# ATTinyx5_Utility_Board.net
KiCad netlist of a schematic drawn in EAGLE
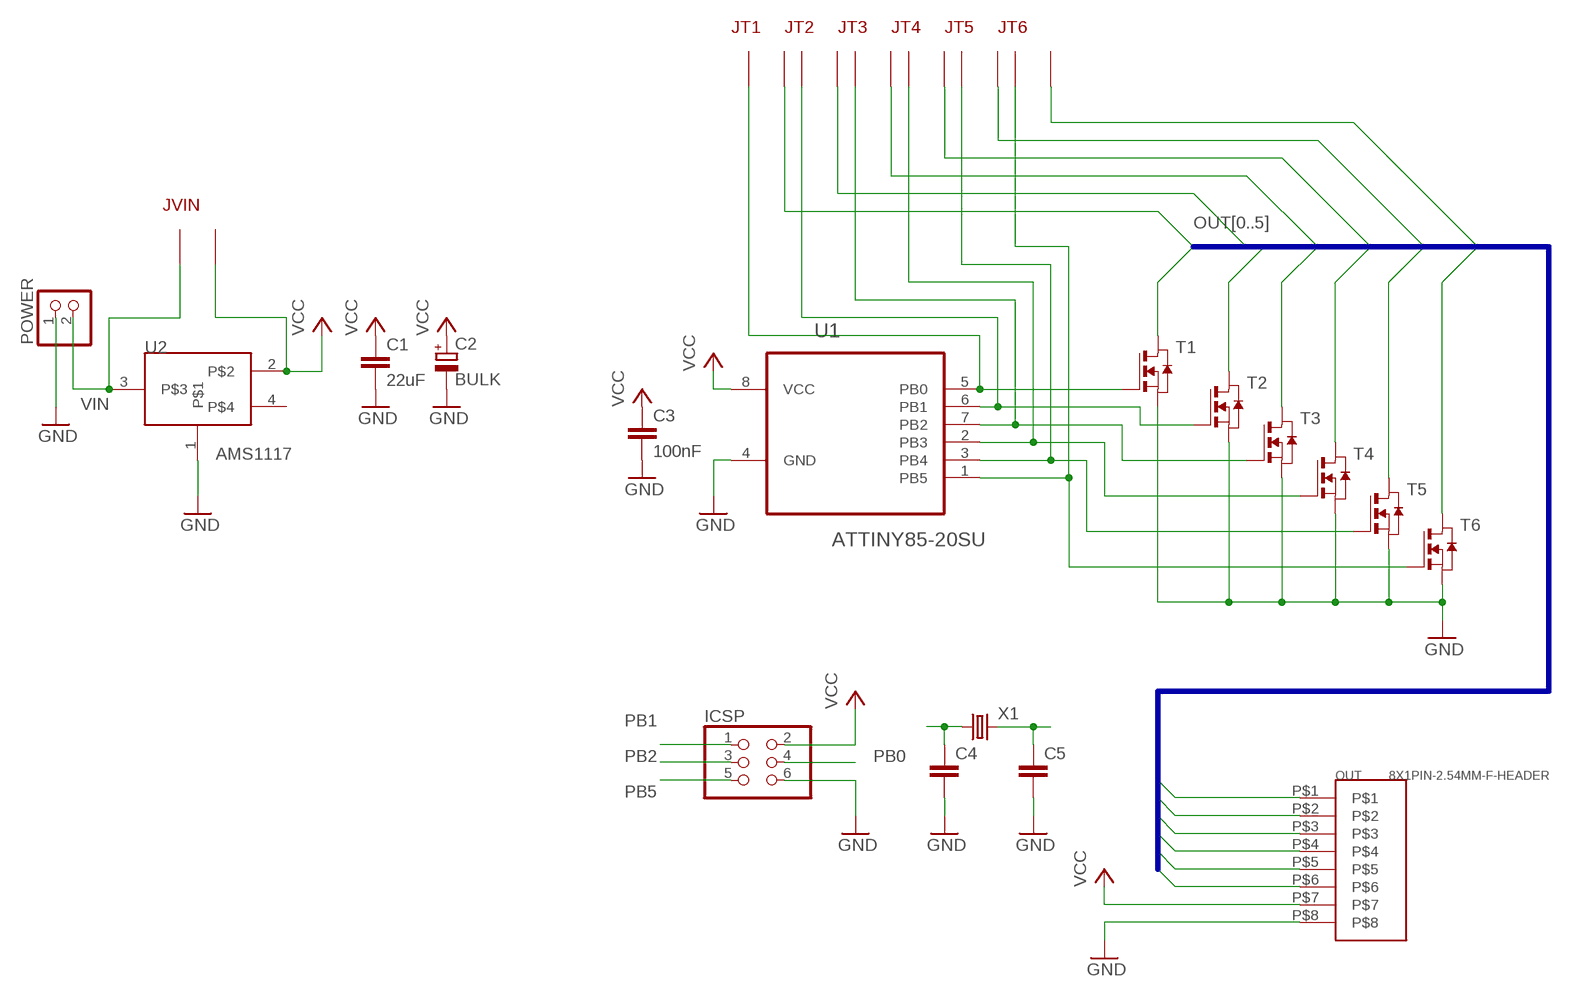
[diagram p0: schematic, sheet 1]

(export (version "E")
  (design (tool "Eeschema 10.0.6"))
  (components
    (comp (ref "C1")
      (value "22uF")
      (footprint "eagle-import:C1206")
      (libsource (lib "eagle-import") (part "C-EUC1206"))
    )
    (comp (ref "C2")
      (value "BULK")
      (footprint "eagle-import:E3,5-10")
      (libsource (lib "eagle-import") (part "CPOL-EUE3.5-10"))
    )
    (comp (ref "C3")
      (value "100nF")
      (footprint "eagle-import:C0805")
      (libsource (lib "eagle-import") (part "C-EUC0805"))
    )
    (comp (ref "C4")
      (value "C-EUC0805")
      (footprint "eagle-import:C0805")
      (libsource (lib "eagle-import") (part "C-EUC0805"))
    )
    (comp (ref "C5")
      (value "C-EUC0805")
      (footprint "eagle-import:C0805")
      (libsource (lib "eagle-import") (part "C-EUC0805"))
    )
    (comp (ref "ICSP")
      (value "PINHD-2X3")
      (footprint "eagle-import:2X03")
      (libsource (lib "eagle-import") (part "PINHD-2X3"))
    )
    (comp (ref "JT1")
      (value "SOLDER_JUMPER")
      (footprint "eagle-import:1206")
      (libsource (lib "eagle-import") (part "SOLDER_JUMPER"))
    )
    (comp (ref "JT2")
      (value "SOLDER_JUMPER")
      (footprint "eagle-import:1206")
      (libsource (lib "eagle-import") (part "SOLDER_JUMPER"))
    )
    (comp (ref "JT3")
      (value "SOLDER_JUMPER")
      (footprint "eagle-import:1206")
      (libsource (lib "eagle-import") (part "SOLDER_JUMPER"))
    )
    (comp (ref "JT4")
      (value "SOLDER_JUMPER")
      (footprint "eagle-import:1206")
      (libsource (lib "eagle-import") (part "SOLDER_JUMPER"))
    )
    (comp (ref "JT5")
      (value "SOLDER_JUMPER")
      (footprint "eagle-import:1206")
      (libsource (lib "eagle-import") (part "SOLDER_JUMPER"))
    )
    (comp (ref "JT6")
      (value "SOLDER_JUMPER")
      (footprint "eagle-import:1206")
      (libsource (lib "eagle-import") (part "SOLDER_JUMPER"))
    )
    (comp (ref "JVIN")
      (value "SOLDER_JUMPER")
      (footprint "eagle-import:1206")
      (libsource (lib "eagle-import") (part "SOLDER_JUMPER"))
    )
    (comp (ref "OUT")
      (value "8X1PIN-2.54MM-F-HEADER")
      (footprint "eagle-import:8X1-2.54MM")
      (libsource (lib "eagle-import") (part "8X1PIN-2.54MM-F-HEADER"))
    )
    (comp (ref "POWER")
      (value "PINHD-1X2")
      (footprint "eagle-import:1X02")
      (libsource (lib "eagle-import") (part "PINHD-1X2"))
    )
    (comp (ref "T1")
      (value "NMOSSOT23")
      (footprint "eagle-import:SOT-23")
      (libsource (lib "eagle-import") (part "NMOSSOT23"))
    )
    (comp (ref "T2")
      (value "NMOSSOT23")
      (footprint "eagle-import:SOT-23")
      (libsource (lib "eagle-import") (part "NMOSSOT23"))
    )
    (comp (ref "T3")
      (value "NMOSSOT23")
      (footprint "eagle-import:SOT-23")
      (libsource (lib "eagle-import") (part "NMOSSOT23"))
    )
    (comp (ref "T4")
      (value "NMOSSOT23")
      (footprint "eagle-import:SOT-23")
      (libsource (lib "eagle-import") (part "NMOSSOT23"))
    )
    (comp (ref "T5")
      (value "NMOSSOT23")
      (footprint "eagle-import:SOT-23")
      (libsource (lib "eagle-import") (part "NMOSSOT23"))
    )
    (comp (ref "T6")
      (value "NMOSSOT23")
      (footprint "eagle-import:SOT-23")
      (libsource (lib "eagle-import") (part "NMOSSOT23"))
    )
    (comp (ref "U1")
      (value "ATTINY85-20SU")
      (footprint "eagle-import:SOIC127P798X216-8N")
      (libsource (lib "eagle-import") (part "ATTINY85-20SU"))
    )
    (comp (ref "U2")
      (value "AMS1117")
      (footprint "eagle-import:SOT223")
      (libsource (lib "eagle-import") (part "ASM1117-3.3"))
    )
    (comp (ref "X1")
      (value "CRYSTALSM49")
      (footprint "eagle-import:SM49")
      (libsource (lib "eagle-import") (part "CRYSTALSM49"))
    )
  )
  (nets
    (net (code "1") (name "/OUT0") (class "Default")
      (node (ref "JT1") (pin "P$2") (pinfunction "P$2_P$2") (pintype "bidirectional"))
      (node (ref "OUT") (pin "P$1") (pinfunction "P$1_P$1") (pintype "bidirectional"))
      (node (ref "T1") (pin "1") (pinfunction "D_1") (pintype "passive"))
    )
    (net (code "2") (name "/OUT1") (class "Default")
      (node (ref "JT2") (pin "P$2") (pinfunction "P$2_P$2") (pintype "bidirectional"))
      (node (ref "OUT") (pin "P$2") (pinfunction "P$2_P$2") (pintype "bidirectional"))
      (node (ref "T2") (pin "1") (pinfunction "D_1") (pintype "passive"))
    )
    (net (code "3") (name "/OUT2") (class "Default")
      (node (ref "JT3") (pin "P$2") (pinfunction "P$2_P$2") (pintype "bidirectional"))
      (node (ref "OUT") (pin "P$3") (pinfunction "P$3_P$3") (pintype "bidirectional"))
      (node (ref "T3") (pin "1") (pinfunction "D_1") (pintype "passive"))
    )
    (net (code "4") (name "/OUT3") (class "Default")
      (node (ref "JT4") (pin "P$2") (pinfunction "P$2_P$2") (pintype "bidirectional"))
      (node (ref "OUT") (pin "P$4") (pinfunction "P$4_P$4") (pintype "bidirectional"))
      (node (ref "T4") (pin "1") (pinfunction "D_1") (pintype "passive"))
    )
    (net (code "5") (name "/OUT4") (class "Default")
      (node (ref "JT5") (pin "P$2") (pinfunction "P$2_P$2") (pintype "bidirectional"))
      (node (ref "OUT") (pin "P$5") (pinfunction "P$5_P$5") (pintype "bidirectional"))
      (node (ref "T5") (pin "1") (pinfunction "D_1") (pintype "passive"))
    )
    (net (code "6") (name "/OUT5") (class "Default")
      (node (ref "JT6") (pin "P$2") (pinfunction "P$2_P$2") (pintype "bidirectional"))
      (node (ref "OUT") (pin "P$6") (pinfunction "P$6_P$6") (pintype "bidirectional"))
      (node (ref "T6") (pin "1") (pinfunction "D_1") (pintype "passive"))
    )
    (net (code "7") (name "/PB0") (class "Default")
      (node (ref "ICSP") (pin "4") (pinfunction "4_4") (pintype "passive"))
      (node (ref "JT1") (pin "P$1") (pinfunction "P$1_P$1") (pintype "bidirectional"))
      (node (ref "T1") (pin "3") (pinfunction "G_3") (pintype "passive"))
      (node (ref "U1") (pin "5") (pinfunction "PB0_5") (pintype "bidirectional"))
    )
    (net (code "8") (name "/PB1") (class "Default")
      (node (ref "ICSP") (pin "1") (pinfunction "1_1") (pintype "passive"))
      (node (ref "JT2") (pin "P$1") (pinfunction "P$1_P$1") (pintype "bidirectional"))
      (node (ref "T2") (pin "3") (pinfunction "G_3") (pintype "passive"))
      (node (ref "U1") (pin "6") (pinfunction "PB1_6") (pintype "bidirectional"))
    )
    (net (code "9") (name "/PB2") (class "Default")
      (node (ref "ICSP") (pin "3") (pinfunction "3_3") (pintype "passive"))
      (node (ref "JT3") (pin "P$1") (pinfunction "P$1_P$1") (pintype "bidirectional"))
      (node (ref "T3") (pin "3") (pinfunction "G_3") (pintype "passive"))
      (node (ref "U1") (pin "7") (pinfunction "PB2_7") (pintype "bidirectional"))
    )
    (net (code "10") (name "/PB3") (class "Default")
      (node (ref "C4") (pin "1") (pinfunction "1_1") (pintype "passive"))
      (node (ref "JT4") (pin "P$1") (pinfunction "P$1_P$1") (pintype "bidirectional"))
      (node (ref "T4") (pin "3") (pinfunction "G_3") (pintype "passive"))
      (node (ref "U1") (pin "2") (pinfunction "PB3_2") (pintype "bidirectional"))
      (node (ref "X1") (pin "1") (pinfunction "1_1") (pintype "passive"))
    )
    (net (code "11") (name "/PB4") (class "Default")
      (node (ref "C5") (pin "1") (pinfunction "1_1") (pintype "passive"))
      (node (ref "JT5") (pin "P$1") (pinfunction "P$1_P$1") (pintype "bidirectional"))
      (node (ref "T5") (pin "3") (pinfunction "G_3") (pintype "passive"))
      (node (ref "U1") (pin "3") (pinfunction "PB4_3") (pintype "bidirectional"))
      (node (ref "X1") (pin "2") (pinfunction "2_2") (pintype "passive"))
    )
    (net (code "12") (name "/PB5") (class "Default")
      (node (ref "ICSP") (pin "5") (pinfunction "5_5") (pintype "passive"))
      (node (ref "JT6") (pin "P$1") (pinfunction "P$1_P$1") (pintype "bidirectional"))
      (node (ref "T6") (pin "3") (pinfunction "G_3") (pintype "passive"))
      (node (ref "U1") (pin "1") (pinfunction "PB5_1") (pintype "bidirectional"))
    )
    (net (code "13") (name "/VIN") (class "Default")
      (node (ref "JVIN") (pin "P$1") (pinfunction "P$1_P$1") (pintype "bidirectional"))
      (node (ref "POWER") (pin "2") (pinfunction "2_2") (pintype "passive"))
      (node (ref "U2") (pin "3") (pinfunction "P$3_3") (pintype "bidirectional"))
    )
    (net (code "14") (name "GND") (class "Default")
      (node (ref "C1") (pin "2") (pinfunction "2_2") (pintype "passive"))
      (node (ref "C2") (pin "-") (pinfunction "-_-") (pintype "passive"))
      (node (ref "C3") (pin "2") (pinfunction "2_2") (pintype "passive"))
      (node (ref "C4") (pin "2") (pinfunction "2_2") (pintype "passive"))
      (node (ref "C5") (pin "2") (pinfunction "2_2") (pintype "passive"))
      (node (ref "ICSP") (pin "6") (pinfunction "6_6") (pintype "passive"))
      (node (ref "OUT") (pin "P$8") (pinfunction "P$8_P$8") (pintype "bidirectional"))
      (node (ref "POWER") (pin "1") (pinfunction "1_1") (pintype "passive"))
      (node (ref "T1") (pin "2") (pinfunction "S_2") (pintype "passive"))
      (node (ref "T2") (pin "2") (pinfunction "S_2") (pintype "passive"))
      (node (ref "T3") (pin "2") (pinfunction "S_2") (pintype "passive"))
      (node (ref "T4") (pin "2") (pinfunction "S_2") (pintype "passive"))
      (node (ref "T5") (pin "2") (pinfunction "S_2") (pintype "passive"))
      (node (ref "T6") (pin "2") (pinfunction "S_2") (pintype "passive"))
      (node (ref "U1") (pin "4") (pinfunction "GND_4") (pintype "passive"))
      (node (ref "U2") (pin "1") (pinfunction "P$1_1") (pintype "bidirectional"))
    )
    (net (code "15") (name "VCC") (class "Default")
      (node (ref "C1") (pin "1") (pinfunction "1_1") (pintype "passive"))
      (node (ref "C2") (pin "+") (pinfunction "+_+") (pintype "passive"))
      (node (ref "C3") (pin "1") (pinfunction "1_1") (pintype "passive"))
      (node (ref "ICSP") (pin "2") (pinfunction "2_2") (pintype "passive"))
      (node (ref "JVIN") (pin "P$2") (pinfunction "P$2_P$2") (pintype "bidirectional"))
      (node (ref "OUT") (pin "P$7") (pinfunction "P$7_P$7") (pintype "bidirectional"))
      (node (ref "U1") (pin "8") (pinfunction "VCC_8") (pintype "power_in"))
      (node (ref "U2") (pin "2") (pinfunction "P$2_2") (pintype "bidirectional"))
    )
    (net (code "16") (name "unconnected-(U2-P$4-Pad4)") (class "Default")
      (node (ref "U2") (pin "4") (pinfunction "P$4_4") (pintype "bidirectional"))
    )
  )
)
